# P08_RS485_RS232_CAN.net
KiCad netlist of a schematic drawn in Altium Designer
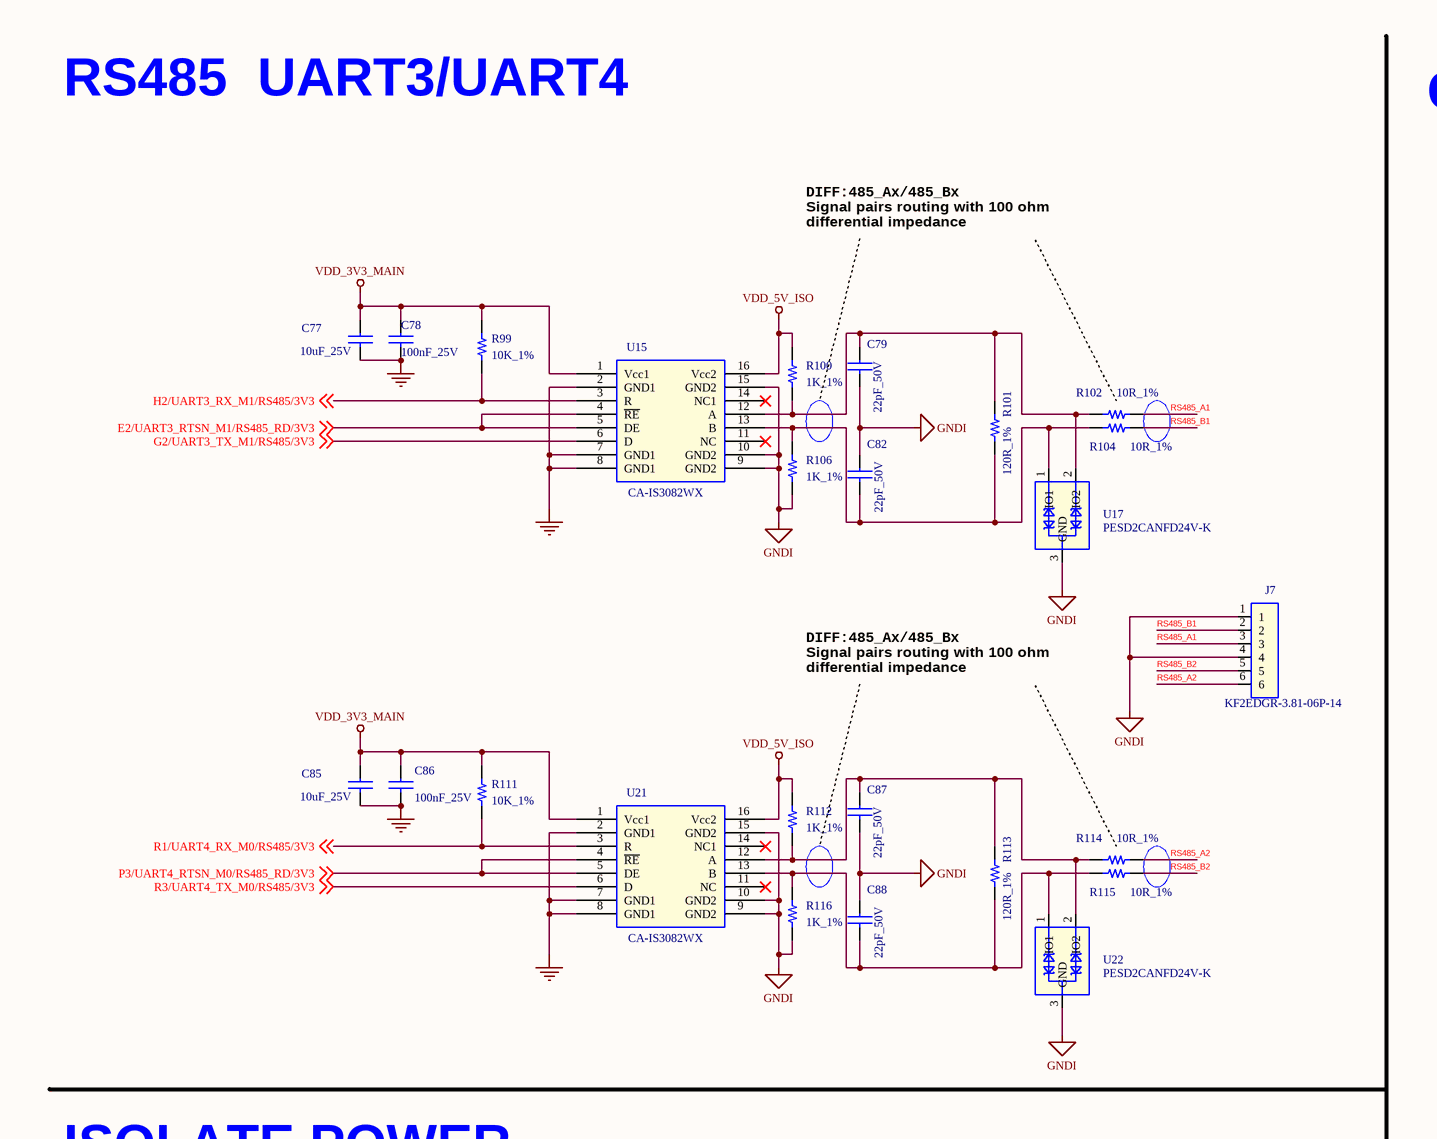
[diagram p0: P08_RS485_RS232_CAN.SchDoc, top left]
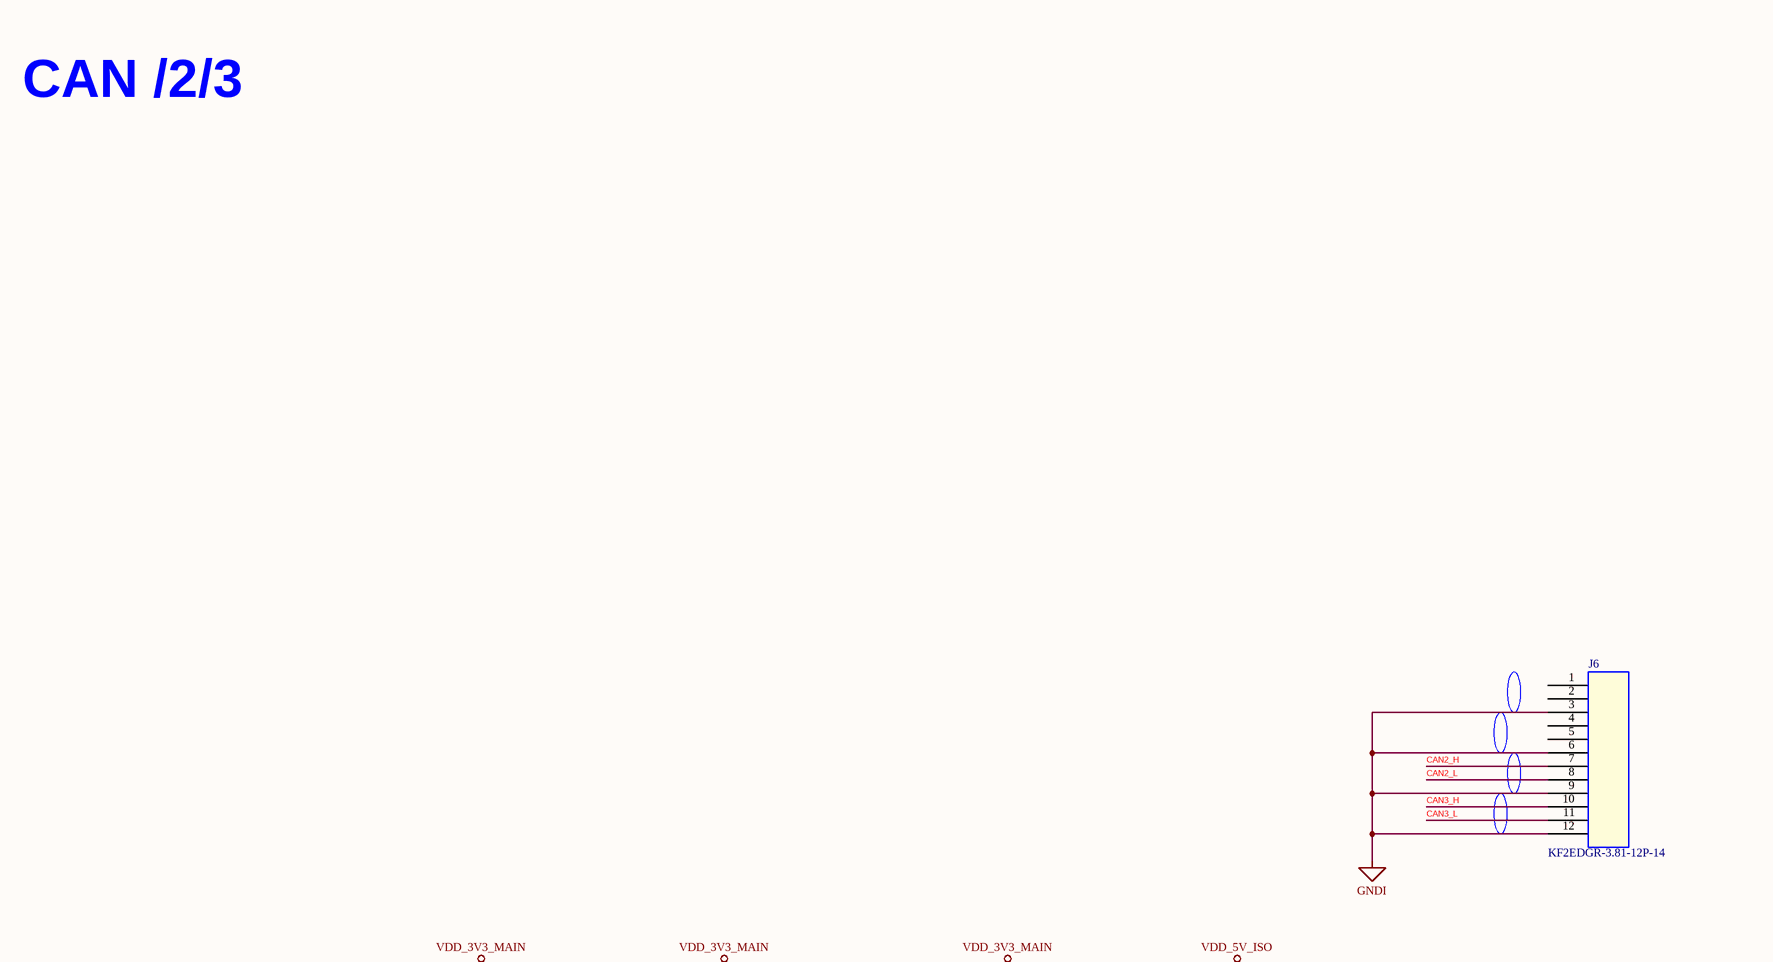
[diagram p1: P08_RS485_RS232_CAN.SchDoc, top right]
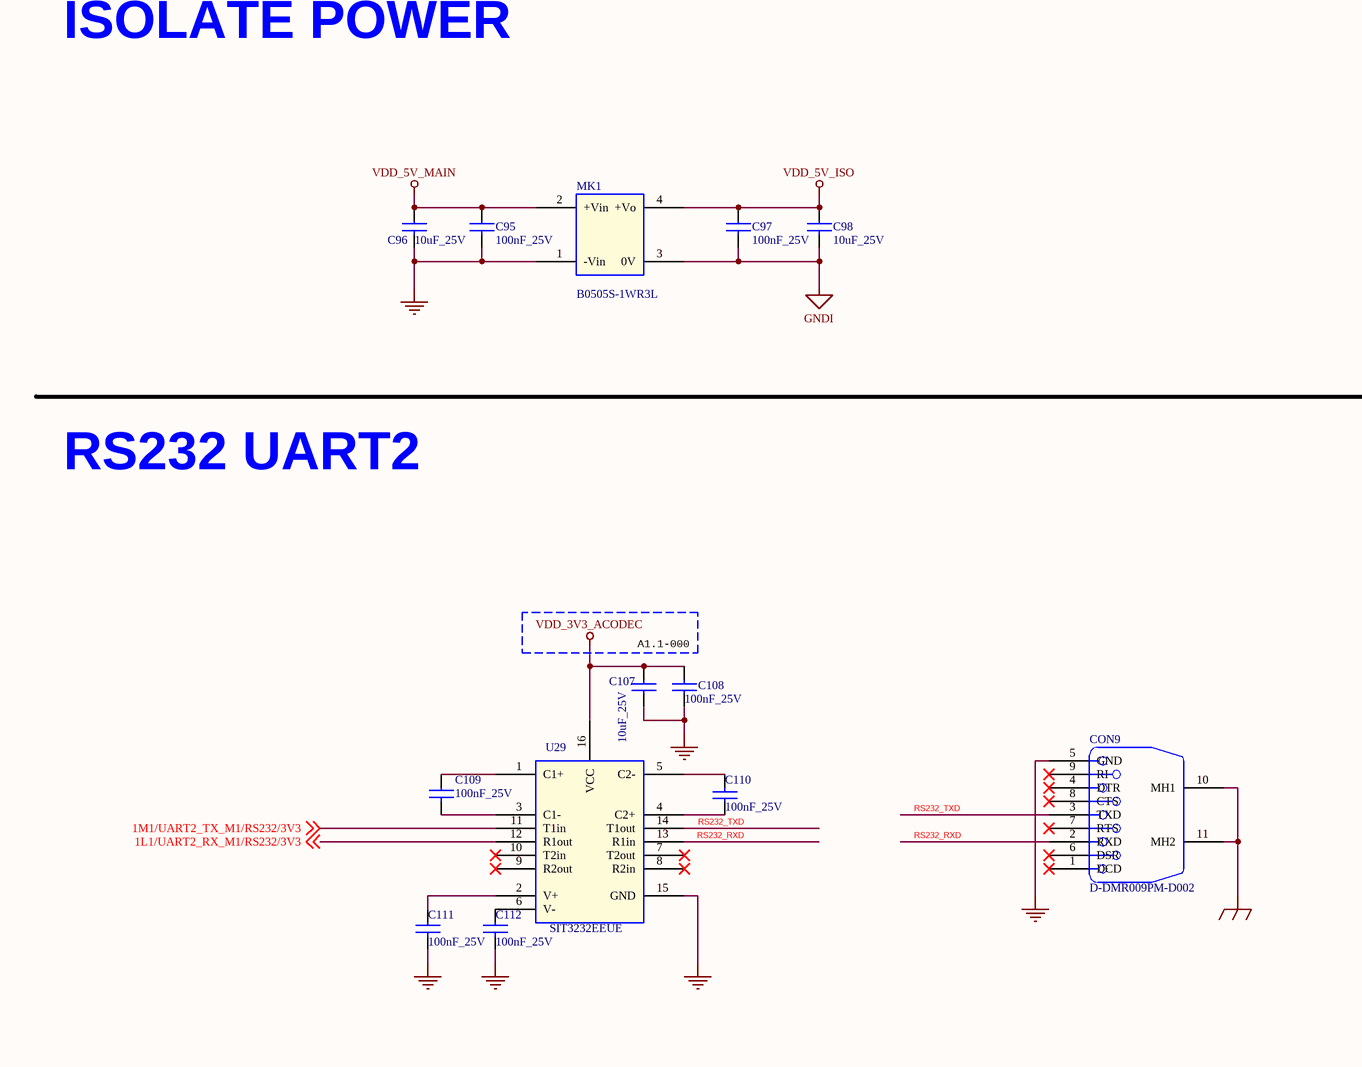
[diagram p2: P08_RS485_RS232_CAN.SchDoc, bottom left]
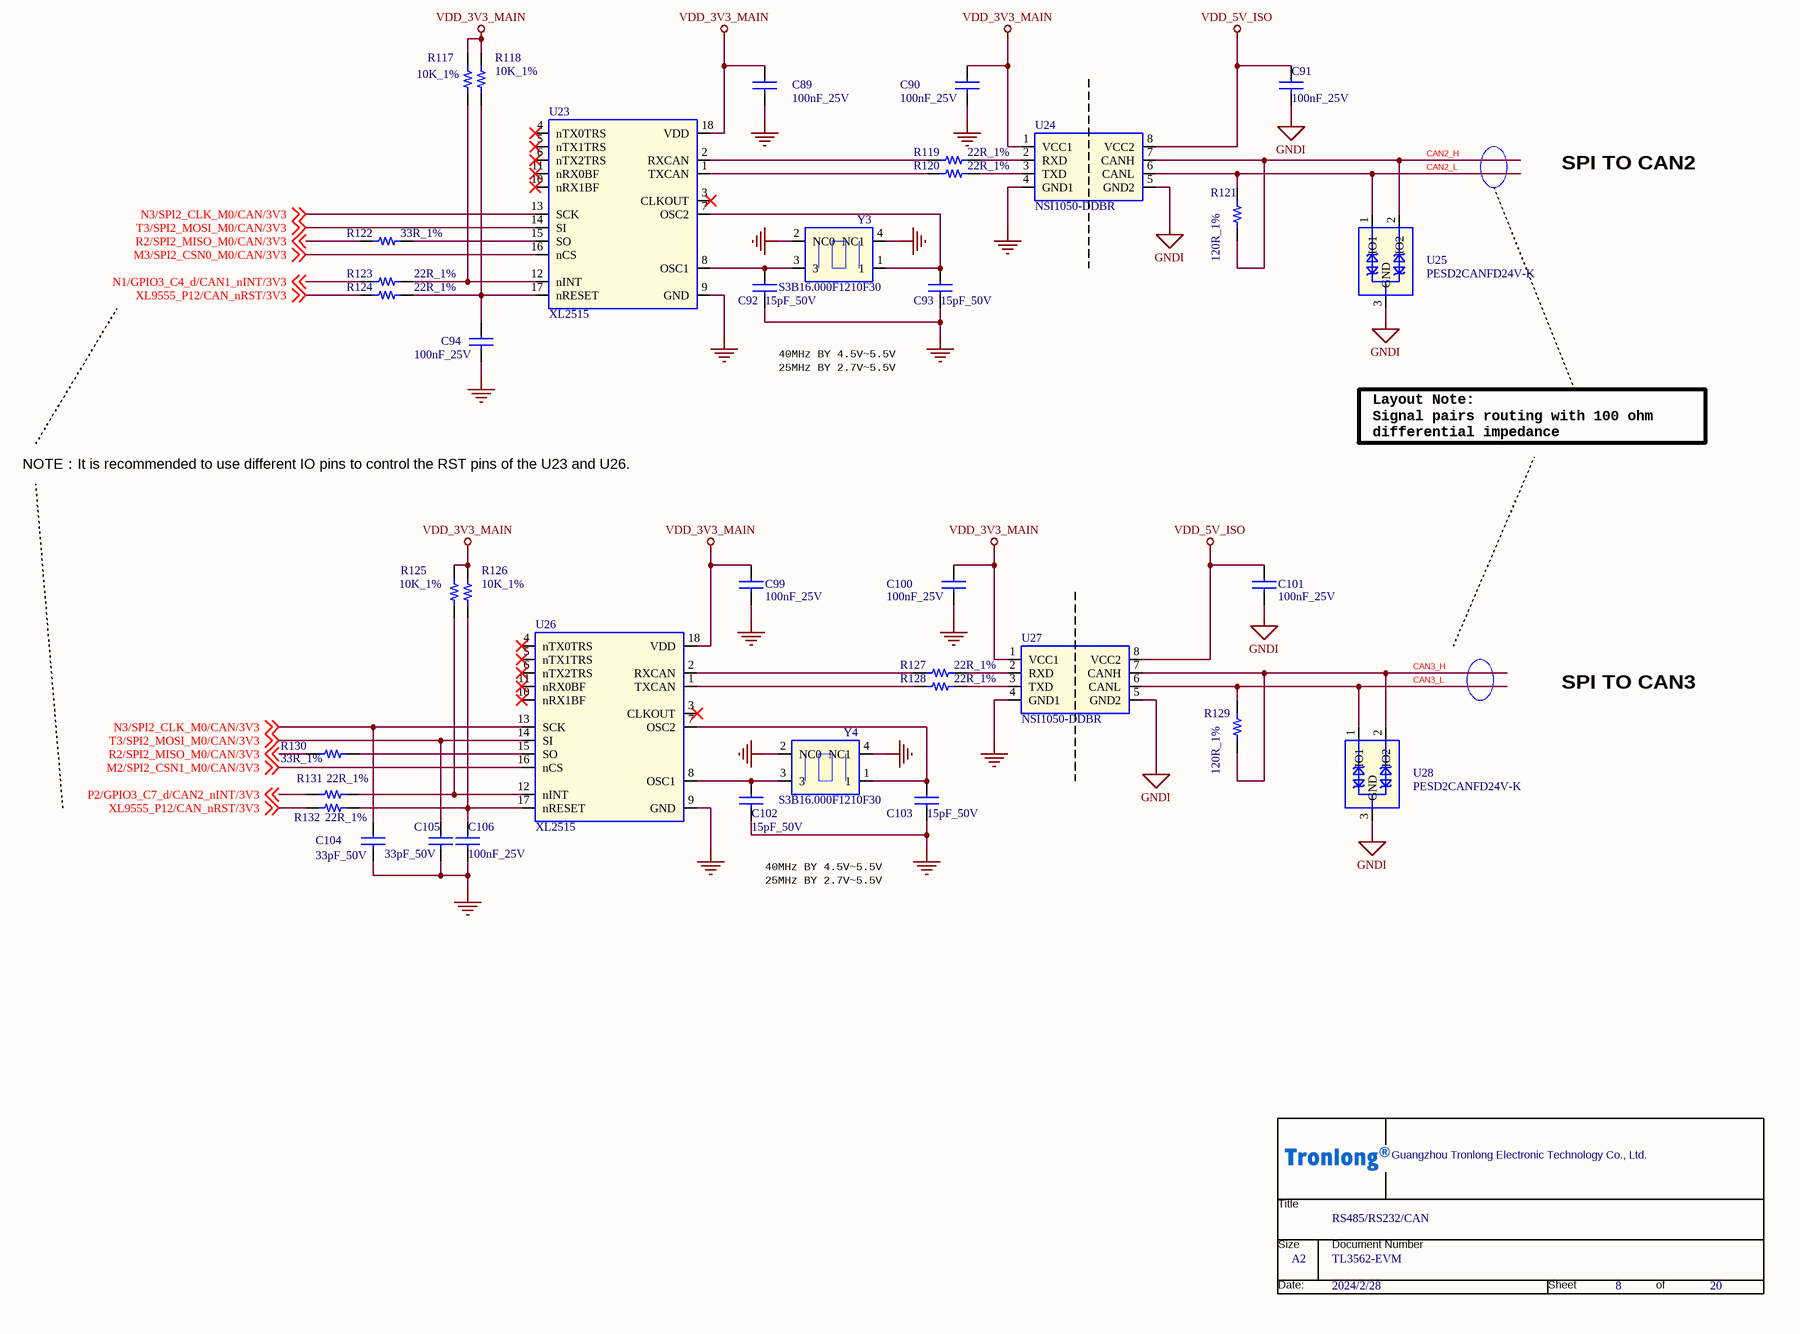
[diagram p3: P08_RS485_RS232_CAN.SchDoc, bottom right]

(export (version "E")
  (design (tool "Eeschema 10.0.6"))
  (components
    (comp (ref "C77")
      (value "10uF_25V")
      (footprint "C0603")
      (description "贴片陶瓷电容,10uF,10%,10V,X5R")
      (libsource (lib "*") (part "CAP NP_Dup3"))
    )
    (comp (ref "C78")
      (value "100nF_25V")
      (footprint "C0402")
      (description "贴片陶瓷电容,100nF,10%,25V,X5R")
      (libsource (lib "*") (part "CAP NP_Dup3"))
    )
    (comp (ref "C79")
      (value "22pF_50V")
      (footprint "C0603")
      (description "贴片陶瓷电容,22pF,5%,50V,C0G")
      (libsource (lib "*") (part "CAP NP_Dup3"))
    )
    (comp (ref "C82")
      (value "22pF_50V")
      (footprint "C0603")
      (description "贴片陶瓷电容,22pF,5%,50V,C0G")
      (libsource (lib "*") (part "CAP NP_Dup3"))
    )
    (comp (ref "C85")
      (value "10uF_25V")
      (footprint "C0603")
      (description "贴片陶瓷电容,10uF,10%,10V,X5R")
      (libsource (lib "*") (part "CAP NP_Dup3"))
    )
    (comp (ref "C86")
      (value "100nF_25V")
      (footprint "C0402")
      (description "贴片陶瓷电容,100nF,10%,25V,X5R")
      (libsource (lib "*") (part "CAP NP_Dup3"))
    )
    (comp (ref "C87")
      (value "22pF_50V")
      (footprint "C0603")
      (description "贴片陶瓷电容,22pF,5%,50V,C0G")
      (libsource (lib "*") (part "CAP NP_Dup3"))
    )
    (comp (ref "C88")
      (value "22pF_50V")
      (footprint "C0603")
      (description "贴片陶瓷电容,22pF,5%,50V,C0G")
      (libsource (lib "*") (part "CAP NP_Dup3"))
    )
    (comp (ref "C89")
      (value "100nF_25V")
      (footprint "C0402")
      (description "贴片陶瓷电容,100nF,10%,25V,X5R")
      (libsource (lib "*") (part "CAP NP_Dup1"))
    )
    (comp (ref "C90")
      (value "100nF_25V")
      (footprint "C0402")
      (description "贴片陶瓷电容,100nF,10%,25V,X5R")
      (libsource (lib "*") (part "CAP NP_Dup1"))
    )
    (comp (ref "C91")
      (value "100nF_25V")
      (footprint "C0402")
      (description "贴片陶瓷电容,100nF,10%,25V,X5R")
      (libsource (lib "*") (part "CAP NP_Dup1"))
    )
    (comp (ref "C92")
      (value "15pF_50V")
      (footprint "C0402")
      (description "贴片陶瓷电容,15pF,5%,50V,COG")
      (libsource (lib "*") (part "CAP NP_Dup1"))
    )
    (comp (ref "C93")
      (value "15pF_50V")
      (footprint "C0402")
      (description "贴片陶瓷电容,15pF,5%,50V,COG")
      (libsource (lib "*") (part "CAP NP_Dup1"))
    )
    (comp (ref "C94")
      (value "100nF_25V")
      (footprint "C0402")
      (description "贴片陶瓷电容,100nF,10%,25V,X5R")
      (libsource (lib "*") (part "CAP NP_Dup1"))
    )
    (comp (ref "C95")
      (value "100nF_25V")
      (footprint "C0402")
      (description "贴片陶瓷电容,100nF,10%,25V,X5R")
      (libsource (lib "*") (part "CAP NP_Dup3"))
    )
    (comp (ref "C96")
      (value "10uF_25V")
      (footprint "C0603")
      (description "贴片陶瓷电容,10uF,10%,10V,X5R")
      (libsource (lib "*") (part "CAP NP_Dup3"))
    )
    (comp (ref "C97")
      (value "100nF_25V")
      (footprint "C0402")
      (description "贴片陶瓷电容,100nF,10%,25V,X5R")
      (libsource (lib "*") (part "CAP NP_Dup3"))
    )
    (comp (ref "C98")
      (value "10uF_25V")
      (footprint "C0603")
      (description "贴片陶瓷电容,10uF,10%,10V,X5R")
      (libsource (lib "*") (part "CAP NP_Dup3"))
    )
    (comp (ref "C99")
      (value "100nF_25V")
      (footprint "C0402")
      (description "贴片陶瓷电容,100nF,10%,25V,X5R")
      (libsource (lib "*") (part "CAP NP_Dup1"))
    )
    (comp (ref "C100")
      (value "100nF_25V")
      (footprint "C0402")
      (description "贴片陶瓷电容,100nF,10%,25V,X5R")
      (libsource (lib "*") (part "CAP NP_Dup1"))
    )
    (comp (ref "C101")
      (value "100nF_25V")
      (footprint "C0402")
      (description "贴片陶瓷电容,100nF,10%,25V,X5R")
      (libsource (lib "*") (part "CAP NP_Dup1"))
    )
    (comp (ref "C102")
      (value "15pF_50V")
      (footprint "C0402")
      (description "贴片陶瓷电容,15pF,5%,50V,COG")
      (libsource (lib "*") (part "CAP NP_Dup1"))
    )
    (comp (ref "C103")
      (value "15pF_50V")
      (footprint "C0402")
      (description "贴片陶瓷电容,15pF,5%,50V,COG")
      (libsource (lib "*") (part "CAP NP_Dup1"))
    )
    (comp (ref "C104")
      (value "33pF_50V")
      (footprint "C0603")
      (description "贴片陶瓷电容,33pF,5%,50V,COG")
      (libsource (lib "*") (part "CAP NP_Dup1"))
    )
    (comp (ref "C105")
      (value "33pF_50V")
      (footprint "C0603")
      (description "贴片陶瓷电容,33pF,5%,50V,COG")
      (libsource (lib "*") (part "CAP NP_Dup1"))
    )
    (comp (ref "C106")
      (value "100nF_25V")
      (footprint "C0402")
      (description "贴片陶瓷电容,100nF,10%,25V,X5R")
      (libsource (lib "*") (part "CAP NP_Dup1"))
    )
    (comp (ref "C107")
      (value "10uF_25V")
      (footprint "C0603")
      (description "贴片陶瓷电容,10uF,10%,10V,X5R")
      (libsource (lib "*") (part "CAP NP_Dup3"))
    )
    (comp (ref "C108")
      (value "100nF_25V")
      (footprint "C0402")
      (description "贴片陶瓷电容,100nF,10%,25V,X5R")
      (libsource (lib "*") (part "CAP NP_Dup3"))
    )
    (comp (ref "C109")
      (value "100nF_25V")
      (footprint "C0402")
      (description "贴片陶瓷电容,100nF,10%,25V,X5R")
      (libsource (lib "*") (part "CAP NP_Dup3"))
    )
    (comp (ref "C110")
      (value "100nF_25V")
      (footprint "C0402")
      (description "贴片陶瓷电容,100nF,10%,25V,X5R")
      (libsource (lib "*") (part "CAP NP_Dup3"))
    )
    (comp (ref "C111")
      (value "100nF_25V")
      (footprint "C0402")
      (description "贴片陶瓷电容,100nF,10%,25V,X5R")
      (libsource (lib "*") (part "CAP NP_Dup3"))
    )
    (comp (ref "C112")
      (value "100nF_25V")
      (footprint "C0402")
      (description "贴片陶瓷电容,100nF,10%,25V,X5R")
      (libsource (lib "*") (part "CAP NP_Dup3"))
    )
    (comp (ref "CON9")
      (value "D-DMR009PM-D002")
      (footprint "CON_DB9")
      (description "DB9,9PIN,90度,公头,黑色,插件")
      (fields (field (name "MANUFACTURER") "深圳市灿科盟实业有限公司（ckmtw）"))
      (libsource (lib "*") (part "DB9_1"))
    )
    (comp (ref "J6")
      (value "KF2EDGR-3.81-12P-14")
      (footprint "KF2EDGR-3d81-12P")
      (description "端子座,12PIN,间距3.81MM,90度,插件")
      (fields
        (field (name "MANUFACTURER") "慈溪市科发电子有限公司（KEFA）")
        (field (name "MANUFACTURER PARTNUMBER") "KF2EDGR-3.81-12P")
      )
      (libsource (lib "*") (part "CON10_0"))
    )
    (comp (ref "J7")
      (value "KF2EDGR-3.81-06P-14")
      (footprint "kf2eg_3_81-6p")
      (description "端子座,6PIN,间距3.81MM,90度,插件")
      (fields
        (field (name "MANUFACTURER") "慈溪市科发电子有限公司（KEFA）")
        (field (name "MANUFACTURER PARTNUMBER") "KF2EDGR-3.81-06P")
      )
      (libsource (lib "*") (part "CON6"))
    )
    (comp (ref "MK1")
      (value "B0505S-1WR3L")
      (footprint "DIP4_B0505S_1W")
      (description "DC-DC隔离电源,B0505S-1WR3L,输入电压5V,输出电压5V,输出电流max/min=200/20mA,效率max/min=78/82")
      (fields (field (name "MANUFACTURER") "广州金升阳科技有限公司（MORNSUN）"))
      (libsource (lib "*") (part "B_S-2W_1"))
    )
    (comp (ref "R99")
      (value "10K_1%")
      (footprint "R0402")
      (description "贴片电阻,10K,±1%,1/16W")
      (libsource (lib "*") (part "Resistor_Dup3"))
    )
    (comp (ref "R100")
      (value "1K_1%")
      (footprint "R0402")
      (description "贴片电阻,1K,±1%,1/16W")
      (libsource (lib "*") (part "Resistor_Dup3"))
    )
    (comp (ref "R101")
      (value "120R_1%")
      (footprint "R0805")
      (description "贴片电阻,120R,±1%,1/8W")
      (libsource (lib "*") (part "Resistor_Dup3"))
    )
    (comp (ref "R102")
      (value "10R_1%")
      (footprint "R0603")
      (description "贴片电阻,10R,±1%,1/10W")
      (libsource (lib "*") (part "Resistor_Dup3"))
    )
    (comp (ref "R104")
      (value "10R_1%")
      (footprint "R0603")
      (description "贴片电阻,10R,±1%,1/10W")
      (libsource (lib "*") (part "Resistor_Dup3"))
    )
    (comp (ref "R106")
      (value "1K_1%")
      (footprint "R0402")
      (description "贴片电阻,1K,±1%,1/16W")
      (libsource (lib "*") (part "Resistor_Dup3"))
    )
    (comp (ref "R111")
      (value "10K_1%")
      (footprint "R0402")
      (description "贴片电阻,10K,±1%,1/16W")
      (libsource (lib "*") (part "Resistor_Dup3"))
    )
    (comp (ref "R112")
      (value "1K_1%")
      (footprint "R0402")
      (description "贴片电阻,1K,±1%,1/16W")
      (libsource (lib "*") (part "Resistor_Dup3"))
    )
    (comp (ref "R113")
      (value "120R_1%")
      (footprint "R0805")
      (description "贴片电阻,120R,±1%,1/8W")
      (libsource (lib "*") (part "Resistor_Dup3"))
    )
    (comp (ref "R114")
      (value "10R_1%")
      (footprint "R0603")
      (description "贴片电阻,10R,±1%,1/10W")
      (libsource (lib "*") (part "Resistor_Dup3"))
    )
    (comp (ref "R115")
      (value "10R_1%")
      (footprint "R0603")
      (description "贴片电阻,10R,±1%,1/10W")
      (libsource (lib "*") (part "Resistor_Dup3"))
    )
    (comp (ref "R116")
      (value "1K_1%")
      (footprint "R0402")
      (description "贴片电阻,1K,±1%,1/16W")
      (libsource (lib "*") (part "Resistor_Dup3"))
    )
    (comp (ref "R117")
      (value "10K_1%")
      (footprint "R0402")
      (description "贴片电阻,10K,±1%,1/16W")
      (libsource (lib "*") (part "R 1%"))
    )
    (comp (ref "R118")
      (value "10K_1%")
      (footprint "R0402")
      (description "贴片电阻,10K,±1%,1/16W")
      (libsource (lib "*") (part "R 1%"))
    )
    (comp (ref "R119")
      (value "22R_1%")
      (footprint "R0402")
      (description "贴片电阻,22R,±1%,1/16W")
      (libsource (lib "*") (part "R 1%"))
    )
    (comp (ref "R120")
      (value "22R_1%")
      (footprint "R0402")
      (description "贴片电阻,22R,±1%,1/16W")
      (libsource (lib "*") (part "R 1%"))
    )
    (comp (ref "R121")
      (value "120R_1%")
      (footprint "R0805")
      (description "贴片电阻,120R,±1%,1/8W")
      (libsource (lib "*") (part "R 1%"))
    )
    (comp (ref "R122")
      (value "33R_1%")
      (footprint "R0402")
      (description "贴片电阻,33R,±1%,1/16W")
      (libsource (lib "*") (part "R 1%"))
    )
    (comp (ref "R123")
      (value "22R_1%")
      (footprint "R0402")
      (description "贴片电阻,22R,±1%,1/16W")
      (libsource (lib "*") (part "R 1%"))
    )
    (comp (ref "R124")
      (value "22R_1%")
      (footprint "R0402")
      (description "贴片电阻,22R,±1%,1/16W")
      (libsource (lib "*") (part "R 1%"))
    )
    (comp (ref "R125")
      (value "10K_1%")
      (footprint "R0402")
      (description "贴片电阻,10K,±1%,1/16W")
      (libsource (lib "*") (part "R 1%"))
    )
    (comp (ref "R126")
      (value "10K_1%")
      (footprint "R0402")
      (description "贴片电阻,10K,±1%,1/16W")
      (libsource (lib "*") (part "R 1%"))
    )
    (comp (ref "R127")
      (value "22R_1%")
      (footprint "R0402")
      (description "贴片电阻,22R,±1%,1/16W")
      (libsource (lib "*") (part "R 1%"))
    )
    (comp (ref "R128")
      (value "22R_1%")
      (footprint "R0402")
      (description "贴片电阻,22R,±1%,1/16W")
      (libsource (lib "*") (part "R 1%"))
    )
    (comp (ref "R129")
      (value "120R_1%")
      (footprint "R0805")
      (description "贴片电阻,120R,±1%,1/8W")
      (libsource (lib "*") (part "R 1%"))
    )
    (comp (ref "R130")
      (value "33R_1%")
      (footprint "R0402")
      (description "贴片电阻,33R,±1%,1/16W")
      (libsource (lib "*") (part "R 1%"))
    )
    (comp (ref "R131")
      (value "22R_1%")
      (footprint "R0402")
      (description "贴片电阻,22R,±1%,1/16W")
      (libsource (lib "*") (part "R 1%"))
    )
    (comp (ref "R132")
      (value "22R_1%")
      (footprint "R0402")
      (description "贴片电阻,22R,±1%,1/16W")
      (libsource (lib "*") (part "R 1%"))
    )
    (comp (ref "U15")
      (value "CA-IS3082WX")
      (footprint "SOIC16")
      (description "CA-IS308x 隔离 5kV 全/半双工 RS485 收发器")
      (fields (field (name "MANUFACTURER") "上海川土微电子有限公司（Chipanalog）"))
      (libsource (lib "*") (part "ISO3082"))
    )
    (comp (ref "U17")
      (value "PESD2CANFD24V-K")
      (footprint "SOT23-3")
      (description "TVS二极管")
      (fields (field (name "MANUFACTURER") "派克微电子（深圳）有限公司"))
      (libsource (lib "*") (part "PSM712"))
    )
    (comp (ref "U21")
      (value "CA-IS3082WX")
      (footprint "SOIC16")
      (description "CA-IS308x 隔离 5kV 全/半双工 RS485 收发器")
      (fields (field (name "MANUFACTURER") "上海川土微电子有限公司（Chipanalog）"))
      (libsource (lib "*") (part "ISO3082"))
    )
    (comp (ref "U22")
      (value "PESD2CANFD24V-K")
      (footprint "SOT23-3")
      (description "TVS二极管")
      (fields (field (name "MANUFACTURER") "派克微电子（深圳）有限公司"))
      (libsource (lib "*") (part "PSM712"))
    )
    (comp (ref "U23")
      (value "XL2515")
      (footprint "SOIC18")
      (description "带 SPI 接口的独立 CAN 控制器")
      (fields (field (name "MANUFACTURER") "信路达信息技术（厦门）有限（xinluda）"))
      (libsource (lib "*") (part "MCP2510/2515_3"))
    )
    (comp (ref "U24")
      (value "NSI1050-DDBR")
      (footprint "SOP8")
      (description "隔离CAN收发器")
      (fields (field (name "MANUFACTURER") "苏州纳芯微电子股份有限公司（NOVOSENSE）"))
      (libsource (lib "*") (part "ISO1050"))
    )
    (comp (ref "U25")
      (value "PESD2CANFD24V-K")
      (footprint "SOT23-3")
      (description "TVS二极管")
      (fields (field (name "MANUFACTURER") "派克微电子（深圳）有限公司"))
      (libsource (lib "*") (part "PSM712"))
    )
    (comp (ref "U26")
      (value "XL2515")
      (footprint "SOIC18")
      (description "带 SPI 接口的独立 CAN 控制器")
      (fields (field (name "MANUFACTURER") "信路达信息技术（厦门）有限（xinluda）"))
      (libsource (lib "*") (part "MCP2510/2515_2"))
    )
    (comp (ref "U27")
      (value "NSI1050-DDBR")
      (footprint "SOP8")
      (description "隔离CAN收发器")
      (fields (field (name "MANUFACTURER") "苏州纳芯微电子股份有限公司（NOVOSENSE）"))
      (libsource (lib "*") (part "ISO1050"))
    )
    (comp (ref "U28")
      (value "PESD2CANFD24V-K")
      (footprint "SOT23-3")
      (description "TVS二极管")
      (fields (field (name "MANUFACTURER") "派克微电子（深圳）有限公司"))
      (libsource (lib "*") (part "PSM712"))
    )
    (comp (ref "U29")
      (value "SIT3232EEUE")
      (footprint "TSSOP16_PW16")
      (description "RS232收发器")
      (fields (field (name "MANUFACTURER") "江苏芯力特电子科技有限公司（SIT）"))
      (libsource (lib "*") (part "MAX232A_0"))
    )
    (comp (ref "Y3")
      (value "S3B16.000F1210F30")
      (footprint "SMD_3225")
      (description "四脚无源晶振,16MHz,±10ppm,12pF,60Ω,±30ppm")
      (fields (field (name "MANUFACTURER") "深圳市星通时频电子有限公司公司（JSCJ）"))
      (libsource (lib "*") (part "CRYSTAL"))
    )
    (comp (ref "Y4")
      (value "S3B16.000F1210F30")
      (footprint "SMD_3225")
      (description "四脚无源晶振,16MHz,±10ppm,12pF,60Ω,±30ppm")
      (fields (field (name "MANUFACTURER") "深圳市星通时频电子有限公司公司（JSCJ）"))
      (libsource (lib "*") (part "CRYSTAL"))
    )
  )
  (nets
    (net (code "1") (name "/CAN2_H") (class "Default")
      (node (ref "J6") (pin "7") (pinfunction "7_7") (pintype "passive"))
      (node (ref "R121") (pin "1") (pinfunction "1_1") (pintype "passive"))
      (node (ref "U24") (pin "7") (pinfunction "CANH_7") (pintype "passive"))
      (node (ref "U25") (pin "2") (pinfunction "IO2_2") (pintype "passive"))
    )
    (net (code "2") (name "/CAN2_L") (class "Default")
      (node (ref "J6") (pin "8") (pinfunction "8_8") (pintype "passive"))
      (node (ref "R121") (pin "2") (pinfunction "2_2") (pintype "passive"))
      (node (ref "U24") (pin "6") (pinfunction "CANL_6") (pintype "passive"))
      (node (ref "U25") (pin "1") (pinfunction "IO1_1") (pintype "passive"))
    )
    (net (code "3") (name "/CAN3_H") (class "Default")
      (node (ref "J6") (pin "10") (pinfunction "10_10") (pintype "passive"))
      (node (ref "R129") (pin "1") (pinfunction "1_1") (pintype "passive"))
      (node (ref "U27") (pin "7") (pinfunction "CANH_7") (pintype "passive"))
      (node (ref "U28") (pin "2") (pinfunction "IO2_2") (pintype "passive"))
    )
    (net (code "4") (name "/CAN3_L") (class "Default")
      (node (ref "J6") (pin "11") (pinfunction "11_11") (pintype "passive"))
      (node (ref "R129") (pin "2") (pinfunction "2_2") (pintype "passive"))
      (node (ref "U27") (pin "6") (pinfunction "CANL_6") (pintype "passive"))
      (node (ref "U28") (pin "1") (pinfunction "IO1_1") (pintype "passive"))
    )
    (net (code "5") (name "/RS232_RXD") (class "Default")
      (node (ref "CON9") (pin "2") (pinfunction "RXD_2") (pintype "passive"))
      (node (ref "U29") (pin "13") (pinfunction "R1in_13") (pintype "passive"))
    )
    (net (code "6") (name "/RS232_TXD") (class "Default")
      (node (ref "CON9") (pin "3") (pinfunction "TXD_3") (pintype "passive"))
      (node (ref "U29") (pin "14") (pinfunction "T1out_14") (pintype "passive"))
    )
    (net (code "7") (name "/RS485_A1") (class "Default")
      (node (ref "J7") (pin "3") (pinfunction "3_3") (pintype "passive"))
      (node (ref "R102") (pin "1") (pinfunction "1_1") (pintype "passive"))
    )
    (net (code "8") (name "/RS485_A2") (class "Default")
      (node (ref "J7") (pin "6") (pinfunction "6_6") (pintype "passive"))
      (node (ref "R114") (pin "1") (pinfunction "1_1") (pintype "passive"))
    )
    (net (code "9") (name "/RS485_B1") (class "Default")
      (node (ref "J7") (pin "2") (pinfunction "2_2") (pintype "passive"))
      (node (ref "R104") (pin "1") (pinfunction "1_1") (pintype "passive"))
    )
    (net (code "10") (name "/RS485_B2") (class "Default")
      (node (ref "J7") (pin "5") (pinfunction "5_5") (pintype "passive"))
      (node (ref "R115") (pin "1") (pinfunction "1_1") (pintype "passive"))
    )
    (net (code "11") (name "1L1{slash}UART2_RX_M1{slash}RS232{slash}3V3") (class "Default")
      (node (ref "U29") (pin "12") (pinfunction "R1out_12") (pintype "passive"))
    )
    (net (code "12") (name "1M1{slash}UART2_TX_M1{slash}RS232{slash}3V3") (class "Default")
      (node (ref "U29") (pin "11") (pinfunction "T1in_11") (pintype "passive"))
    )
    (net (code "13") (name "E2{slash}UART3_RTSN_M1{slash}RS485_RD{slash}3V3") (class "Default")
      (node (ref "U15") (pin "4") (pinfunction "~{RE}_4") (pintype "passive"))
      (node (ref "U15") (pin "5") (pinfunction "DE_5") (pintype "passive"))
    )
    (net (code "14") (name "EGND") (class "Default")
      (node (ref "CON9") (pin "10") (pinfunction "MH1_10") (pintype "passive"))
      (node (ref "CON9") (pin "11") (pinfunction "MH2_11") (pintype "passive"))
    )
    (net (code "15") (name "G2{slash}UART3_TX_M1{slash}RS485{slash}3V3") (class "Default")
      (node (ref "U15") (pin "6") (pinfunction "D_6") (pintype "passive"))
    )
    (net (code "16") (name "GND") (class "Default")
      (node (ref "C100") (pin "2") (pinfunction "2_2") (pintype "passive"))
      (node (ref "C102") (pin "2") (pinfunction "2_2") (pintype "passive"))
      (node (ref "C103") (pin "2") (pinfunction "2_2") (pintype "passive"))
      (node (ref "C104") (pin "2") (pinfunction "2_2") (pintype "passive"))
      (node (ref "C105") (pin "2") (pinfunction "2_2") (pintype "passive"))
      (node (ref "C106") (pin "2") (pinfunction "2_2") (pintype "passive"))
      (node (ref "C107") (pin "1") (pinfunction "1_1") (pintype "passive"))
      (node (ref "C108") (pin "1") (pinfunction "1_1") (pintype "passive"))
      (node (ref "C111") (pin "2") (pinfunction "2_2") (pintype "passive"))
      (node (ref "C112") (pin "2") (pinfunction "2_2") (pintype "passive"))
      (node (ref "C77") (pin "2") (pinfunction "2_2") (pintype "passive"))
      (node (ref "C78") (pin "2") (pinfunction "2_2") (pintype "passive"))
      (node (ref "C85") (pin "2") (pinfunction "2_2") (pintype "passive"))
      (node (ref "C86") (pin "2") (pinfunction "2_2") (pintype "passive"))
      (node (ref "C89") (pin "2") (pinfunction "2_2") (pintype "passive"))
      (node (ref "C90") (pin "2") (pinfunction "2_2") (pintype "passive"))
      (node (ref "C92") (pin "2") (pinfunction "2_2") (pintype "passive"))
      (node (ref "C93") (pin "2") (pinfunction "2_2") (pintype "passive"))
      (node (ref "C94") (pin "2") (pinfunction "2_2") (pintype "passive"))
      (node (ref "C95") (pin "2") (pinfunction "2_2") (pintype "passive"))
      (node (ref "C96") (pin "2") (pinfunction "2_2") (pintype "passive"))
      (node (ref "C99") (pin "2") (pinfunction "2_2") (pintype "passive"))
      (node (ref "CON9") (pin "5") (pinfunction "GND_5") (pintype "power_in"))
      (node (ref "MK1") (pin "1") (pinfunction "-Vin_1") (pintype "passive"))
      (node (ref "U15") (pin "2") (pinfunction "GND1_2") (pintype "power_in"))
      (node (ref "U15") (pin "7") (pinfunction "GND1_7") (pintype "power_in"))
      (node (ref "U15") (pin "8") (pinfunction "GND1_8") (pintype "power_in"))
      (node (ref "U21") (pin "2") (pinfunction "GND1_2") (pintype "power_in"))
      (node (ref "U21") (pin "7") (pinfunction "GND1_7") (pintype "power_in"))
      (node (ref "U21") (pin "8") (pinfunction "GND1_8") (pintype "power_in"))
      (node (ref "U23") (pin "9") (pinfunction "GND_9") (pintype "power_in"))
      (node (ref "U24") (pin "4") (pinfunction "GND1_4") (pintype "power_in"))
      (node (ref "U26") (pin "9") (pinfunction "GND_9") (pintype "power_in"))
      (node (ref "U27") (pin "4") (pinfunction "GND1_4") (pintype "power_in"))
      (node (ref "U29") (pin "15") (pinfunction "GND_15") (pintype "passive"))
      (node (ref "Y3") (pin "2") (pinfunction "NC0_2") (pintype "passive"))
      (node (ref "Y3") (pin "4") (pinfunction "NC1_4") (pintype "passive"))
      (node (ref "Y4") (pin "2") (pinfunction "NC0_2") (pintype "passive"))
      (node (ref "Y4") (pin "4") (pinfunction "NC1_4") (pintype "passive"))
    )
    (net (code "17") (name "GNDI") (class "Default")
      (node (ref "C101") (pin "2") (pinfunction "2_2") (pintype "passive"))
      (node (ref "C79") (pin "2") (pinfunction "2_2") (pintype "passive"))
      (node (ref "C82") (pin "1") (pinfunction "1_1") (pintype "passive"))
      (node (ref "C87") (pin "2") (pinfunction "2_2") (pintype "passive"))
      (node (ref "C88") (pin "1") (pinfunction "1_1") (pintype "passive"))
      (node (ref "C91") (pin "2") (pinfunction "2_2") (pintype "passive"))
      (node (ref "C97") (pin "2") (pinfunction "2_2") (pintype "passive"))
      (node (ref "C98") (pin "2") (pinfunction "2_2") (pintype "passive"))
      (node (ref "J6") (pin "12") (pinfunction "12_12") (pintype "passive"))
      (node (ref "J6") (pin "3") (pinfunction "3_3") (pintype "passive"))
      (node (ref "J6") (pin "6") (pinfunction "6_6") (pintype "passive"))
      (node (ref "J6") (pin "9") (pinfunction "9_9") (pintype "passive"))
      (node (ref "J7") (pin "1") (pinfunction "1_1") (pintype "passive"))
      (node (ref "J7") (pin "4") (pinfunction "4_4") (pintype "passive"))
      (node (ref "MK1") (pin "3") (pinfunction "0V_3") (pintype "passive"))
      (node (ref "R106") (pin "2") (pinfunction "2_2") (pintype "passive"))
      (node (ref "R116") (pin "2") (pinfunction "2_2") (pintype "passive"))
      (node (ref "U15") (pin "10") (pinfunction "GND2_10") (pintype "power_in"))
      (node (ref "U15") (pin "15") (pinfunction "GND2_15") (pintype "power_in"))
      (node (ref "U15") (pin "9") (pinfunction "GND2_9") (pintype "power_in"))
      (node (ref "U17") (pin "3") (pinfunction "GND_3") (pintype "passive"))
      (node (ref "U21") (pin "10") (pinfunction "GND2_10") (pintype "power_in"))
      (node (ref "U21") (pin "15") (pinfunction "GND2_15") (pintype "power_in"))
      (node (ref "U21") (pin "9") (pinfunction "GND2_9") (pintype "power_in"))
      (node (ref "U22") (pin "3") (pinfunction "GND_3") (pintype "passive"))
      (node (ref "U24") (pin "5") (pinfunction "GND2_5") (pintype "power_in"))
      (node (ref "U25") (pin "3") (pinfunction "GND_3") (pintype "passive"))
      (node (ref "U27") (pin "5") (pinfunction "GND2_5") (pintype "power_in"))
      (node (ref "U28") (pin "3") (pinfunction "GND_3") (pintype "passive"))
    )
    (net (code "18") (name "H2{slash}UART3_RX_M1{slash}RS485{slash}3V3") (class "Default")
      (node (ref "R99") (pin "2") (pinfunction "2_2") (pintype "passive"))
      (node (ref "U15") (pin "3") (pinfunction "R_3") (pintype "passive"))
    )
    (net (code "19") (name "M2{slash}SPI2_CSN1_M0{slash}CAN{slash}3V3") (class "Default")
      (node (ref "U26") (pin "16") (pinfunction "nCS_16") (pintype "passive"))
    )
    (net (code "20") (name "M3{slash}SPI2_CSN0_M0{slash}CAN{slash}3V3") (class "Default")
      (node (ref "U23") (pin "16") (pinfunction "nCS_16") (pintype "passive"))
    )
    (net (code "21") (name "N1{slash}GPIO3_C4_d{slash}CAN1_nINT{slash}3V3") (class "Default")
      (node (ref "R123") (pin "1") (pinfunction "1_1") (pintype "passive"))
    )
    (net (code "22") (name "N3{slash}SPI2_CLK_M0{slash}CAN{slash}3V3") (class "Default")
      (node (ref "C104") (pin "1") (pinfunction "1_1") (pintype "passive"))
      (node (ref "U23") (pin "13") (pinfunction "SCK_13") (pintype "passive"))
      (node (ref "U26") (pin "13") (pinfunction "SCK_13") (pintype "passive"))
    )
    (net (code "23") (name "Net-(U15-A)") (class "Default")
      (node (ref "C79") (pin "1") (pinfunction "1_1") (pintype "passive"))
      (node (ref "R100") (pin "2") (pinfunction "2_2") (pintype "passive"))
      (node (ref "R101") (pin "1") (pinfunction "1_1") (pintype "passive"))
      (node (ref "R102") (pin "2") (pinfunction "2_2") (pintype "passive"))
      (node (ref "U15") (pin "12") (pinfunction "A_12") (pintype "passive"))
      (node (ref "U17") (pin "2") (pinfunction "IO2_2") (pintype "passive"))
    )
    (net (code "24") (name "Net-(U15-B)") (class "Default")
      (node (ref "C82") (pin "2") (pinfunction "2_2") (pintype "passive"))
      (node (ref "R101") (pin "2") (pinfunction "2_2") (pintype "passive"))
      (node (ref "R104") (pin "2") (pinfunction "2_2") (pintype "passive"))
      (node (ref "R106") (pin "1") (pinfunction "1_1") (pintype "passive"))
      (node (ref "U15") (pin "13") (pinfunction "B_13") (pintype "passive"))
      (node (ref "U17") (pin "1") (pinfunction "IO1_1") (pintype "passive"))
    )
    (net (code "25") (name "Net-(U21-A)") (class "Default")
      (node (ref "C87") (pin "1") (pinfunction "1_1") (pintype "passive"))
      (node (ref "R112") (pin "2") (pinfunction "2_2") (pintype "passive"))
      (node (ref "R113") (pin "1") (pinfunction "1_1") (pintype "passive"))
      (node (ref "R114") (pin "2") (pinfunction "2_2") (pintype "passive"))
      (node (ref "U21") (pin "12") (pinfunction "A_12") (pintype "passive"))
      (node (ref "U22") (pin "2") (pinfunction "IO2_2") (pintype "passive"))
    )
    (net (code "26") (name "Net-(U21-B)") (class "Default")
      (node (ref "C88") (pin "2") (pinfunction "2_2") (pintype "passive"))
      (node (ref "R113") (pin "2") (pinfunction "2_2") (pintype "passive"))
      (node (ref "R115") (pin "2") (pinfunction "2_2") (pintype "passive"))
      (node (ref "R116") (pin "1") (pinfunction "1_1") (pintype "passive"))
      (node (ref "U21") (pin "13") (pinfunction "B_13") (pintype "passive"))
      (node (ref "U22") (pin "1") (pinfunction "IO1_1") (pintype "passive"))
    )
    (net (code "27") (name "Net-(U23-OSC1)") (class "Default")
      (node (ref "C92") (pin "1") (pinfunction "1_1") (pintype "passive"))
      (node (ref "U23") (pin "8") (pinfunction "OSC1_8") (pintype "passive"))
      (node (ref "Y3") (pin "3") (pinfunction "3_3") (pintype "passive"))
    )
    (net (code "28") (name "Net-(U23-OSC2)") (class "Default")
      (node (ref "C93") (pin "1") (pinfunction "1_1") (pintype "passive"))
      (node (ref "U23") (pin "7") (pinfunction "OSC2_7") (pintype "passive"))
      (node (ref "Y3") (pin "1") (pinfunction "1_1") (pintype "passive"))
    )
    (net (code "29") (name "Net-(U23-RXCAN)") (class "Default")
      (node (ref "R119") (pin "1") (pinfunction "1_1") (pintype "passive"))
      (node (ref "U23") (pin "2") (pinfunction "RXCAN_2") (pintype "passive"))
    )
    (net (code "30") (name "Net-(U23-SO)") (class "Default")
      (node (ref "R122") (pin "2") (pinfunction "2_2") (pintype "passive"))
      (node (ref "U23") (pin "15") (pinfunction "SO_15") (pintype "passive"))
    )
    (net (code "31") (name "Net-(U23-TXCAN)") (class "Default")
      (node (ref "R120") (pin "1") (pinfunction "1_1") (pintype "passive"))
      (node (ref "U23") (pin "1") (pinfunction "TXCAN_1") (pintype "passive"))
    )
    (net (code "32") (name "Net-(U23-nINT)") (class "Default")
      (node (ref "R117") (pin "1") (pinfunction "1_1") (pintype "passive"))
      (node (ref "R123") (pin "2") (pinfunction "2_2") (pintype "passive"))
      (node (ref "U23") (pin "12") (pinfunction "nINT_12") (pintype "passive"))
    )
    (net (code "33") (name "Net-(U23-nRESET)") (class "Default")
      (node (ref "C94") (pin "1") (pinfunction "1_1") (pintype "passive"))
      (node (ref "R118") (pin "1") (pinfunction "1_1") (pintype "passive"))
      (node (ref "R124") (pin "2") (pinfunction "2_2") (pintype "passive"))
      (node (ref "U23") (pin "17") (pinfunction "nRESET_17") (pintype "passive"))
    )
    (net (code "34") (name "Net-(U24-RXD)") (class "Default")
      (node (ref "R119") (pin "2") (pinfunction "2_2") (pintype "passive"))
      (node (ref "U24") (pin "2") (pinfunction "RXD_2") (pintype "passive"))
    )
    (net (code "35") (name "Net-(U24-TXD)") (class "Default")
      (node (ref "R120") (pin "2") (pinfunction "2_2") (pintype "passive"))
      (node (ref "U24") (pin "3") (pinfunction "TXD_3") (pintype "passive"))
    )
    (net (code "36") (name "Net-(U26-OSC1)") (class "Default")
      (node (ref "C102") (pin "1") (pinfunction "1_1") (pintype "passive"))
      (node (ref "U26") (pin "8") (pinfunction "OSC1_8") (pintype "passive"))
      (node (ref "Y4") (pin "3") (pinfunction "3_3") (pintype "passive"))
    )
    (net (code "37") (name "Net-(U26-OSC2)") (class "Default")
      (node (ref "C103") (pin "1") (pinfunction "1_1") (pintype "passive"))
      (node (ref "U26") (pin "7") (pinfunction "OSC2_7") (pintype "passive"))
      (node (ref "Y4") (pin "1") (pinfunction "1_1") (pintype "passive"))
    )
    (net (code "38") (name "Net-(U26-RXCAN)") (class "Default")
      (node (ref "R127") (pin "1") (pinfunction "1_1") (pintype "passive"))
      (node (ref "U26") (pin "2") (pinfunction "RXCAN_2") (pintype "passive"))
    )
    (net (code "39") (name "Net-(U26-SO)") (class "Default")
      (node (ref "R130") (pin "2") (pinfunction "2_2") (pintype "passive"))
      (node (ref "U26") (pin "15") (pinfunction "SO_15") (pintype "passive"))
    )
    (net (code "40") (name "Net-(U26-TXCAN)") (class "Default")
      (node (ref "R128") (pin "1") (pinfunction "1_1") (pintype "passive"))
      (node (ref "U26") (pin "1") (pinfunction "TXCAN_1") (pintype "passive"))
    )
    (net (code "41") (name "Net-(U26-nINT)") (class "Default")
      (node (ref "R125") (pin "1") (pinfunction "1_1") (pintype "passive"))
      (node (ref "R131") (pin "2") (pinfunction "2_2") (pintype "passive"))
      (node (ref "U26") (pin "12") (pinfunction "nINT_12") (pintype "passive"))
    )
    (net (code "42") (name "Net-(U26-nRESET)") (class "Default")
      (node (ref "C106") (pin "1") (pinfunction "1_1") (pintype "passive"))
      (node (ref "R126") (pin "1") (pinfunction "1_1") (pintype "passive"))
      (node (ref "R132") (pin "2") (pinfunction "2_2") (pintype "passive"))
      (node (ref "U26") (pin "17") (pinfunction "nRESET_17") (pintype "passive"))
    )
    (net (code "43") (name "Net-(U27-RXD)") (class "Default")
      (node (ref "R127") (pin "2") (pinfunction "2_2") (pintype "passive"))
      (node (ref "U27") (pin "2") (pinfunction "RXD_2") (pintype "passive"))
    )
    (net (code "44") (name "Net-(U27-TXD)") (class "Default")
      (node (ref "R128") (pin "2") (pinfunction "2_2") (pintype "passive"))
      (node (ref "U27") (pin "3") (pinfunction "TXD_3") (pintype "passive"))
    )
    (net (code "45") (name "Net-(U29-C1+)") (class "Default")
      (node (ref "C109") (pin "1") (pinfunction "1_1") (pintype "passive"))
      (node (ref "U29") (pin "1") (pinfunction "C1+_1") (pintype "passive"))
    )
    (net (code "46") (name "Net-(U29-C1-)") (class "Default")
      (node (ref "C109") (pin "2") (pinfunction "2_2") (pintype "passive"))
      (node (ref "U29") (pin "3") (pinfunction "C1-_3") (pintype "passive"))
    )
    (net (code "47") (name "Net-(U29-C2+)") (class "Default")
      (node (ref "C110") (pin "1") (pinfunction "1_1") (pintype "passive"))
      (node (ref "U29") (pin "4") (pinfunction "C2+_4") (pintype "passive"))
    )
    (net (code "48") (name "Net-(U29-C2-)") (class "Default")
      (node (ref "C110") (pin "2") (pinfunction "2_2") (pintype "passive"))
      (node (ref "U29") (pin "5") (pinfunction "C2-_5") (pintype "passive"))
    )
    (net (code "49") (name "Net-(U29-V+)") (class "Default")
      (node (ref "C111") (pin "1") (pinfunction "1_1") (pintype "passive"))
      (node (ref "U29") (pin "2") (pinfunction "V+_2") (pintype "passive"))
    )
    (net (code "50") (name "Net-(U29-V-)") (class "Default")
      (node (ref "C112") (pin "1") (pinfunction "1_1") (pintype "passive"))
      (node (ref "U29") (pin "6") (pinfunction "V-_6") (pintype "passive"))
    )
    (net (code "51") (name "P2{slash}GPIO3_C7_d{slash}CAN2_nINT{slash}3V3") (class "Default")
      (node (ref "R131") (pin "1") (pinfunction "1_1") (pintype "passive"))
    )
    (net (code "52") (name "P3{slash}UART4_RTSN_M0{slash}RS485_RD{slash}3V3") (class "Default")
      (node (ref "U21") (pin "4") (pinfunction "~{RE}_4") (pintype "passive"))
      (node (ref "U21") (pin "5") (pinfunction "DE_5") (pintype "passive"))
    )
    (net (code "53") (name "R1{slash}UART4_RX_M0{slash}RS485{slash}3V3") (class "Default")
      (node (ref "R111") (pin "2") (pinfunction "2_2") (pintype "passive"))
      (node (ref "U21") (pin "3") (pinfunction "R_3") (pintype "passive"))
    )
    (net (code "54") (name "R2{slash}SPI2_MISO_M0{slash}CAN{slash}3V3") (class "Default")
      (node (ref "R122") (pin "1") (pinfunction "1_1") (pintype "passive"))
      (node (ref "R130") (pin "1") (pinfunction "1_1") (pintype "passive"))
    )
    (net (code "55") (name "R3{slash}UART4_TX_M0{slash}RS485{slash}3V3") (class "Default")
      (node (ref "U21") (pin "6") (pinfunction "D_6") (pintype "passive"))
    )
    (net (code "56") (name "T3{slash}SPI2_MOSI_M0{slash}CAN{slash}3V3") (class "Default")
      (node (ref "C105") (pin "1") (pinfunction "1_1") (pintype "passive"))
      (node (ref "U23") (pin "14") (pinfunction "SI_14") (pintype "passive"))
      (node (ref "U26") (pin "14") (pinfunction "SI_14") (pintype "passive"))
    )
    (net (code "57") (name "VDD_3V3_ACODEC") (class "Default")
      (node (ref "C107") (pin "2") (pinfunction "2_2") (pintype "passive"))
      (node (ref "C108") (pin "2") (pinfunction "2_2") (pintype "passive"))
      (node (ref "U29") (pin "16") (pinfunction "VCC_16") (pintype "passive"))
    )
    (net (code "58") (name "VDD_3V3_MAIN") (class "Default")
      (node (ref "C100") (pin "1") (pinfunction "1_1") (pintype "passive"))
      (node (ref "C77") (pin "1") (pinfunction "1_1") (pintype "passive"))
      (node (ref "C78") (pin "1") (pinfunction "1_1") (pintype "passive"))
      (node (ref "C85") (pin "1") (pinfunction "1_1") (pintype "passive"))
      (node (ref "C86") (pin "1") (pinfunction "1_1") (pintype "passive"))
      (node (ref "C89") (pin "1") (pinfunction "1_1") (pintype "passive"))
      (node (ref "C90") (pin "1") (pinfunction "1_1") (pintype "passive"))
      (node (ref "C99") (pin "1") (pinfunction "1_1") (pintype "passive"))
      (node (ref "R111") (pin "1") (pinfunction "1_1") (pintype "passive"))
      (node (ref "R117") (pin "2") (pinfunction "2_2") (pintype "passive"))
      (node (ref "R118") (pin "2") (pinfunction "2_2") (pintype "passive"))
      (node (ref "R125") (pin "2") (pinfunction "2_2") (pintype "passive"))
      (node (ref "R126") (pin "2") (pinfunction "2_2") (pintype "passive"))
      (node (ref "R99") (pin "1") (pinfunction "1_1") (pintype "passive"))
      (node (ref "U15") (pin "1") (pinfunction "Vcc1_1") (pintype "passive"))
      (node (ref "U21") (pin "1") (pinfunction "Vcc1_1") (pintype "passive"))
      (node (ref "U23") (pin "18") (pinfunction "VDD_18") (pintype "power_in"))
      (node (ref "U24") (pin "1") (pinfunction "VCC1_1") (pintype "power_in"))
      (node (ref "U26") (pin "18") (pinfunction "VDD_18") (pintype "power_in"))
      (node (ref "U27") (pin "1") (pinfunction "VCC1_1") (pintype "power_in"))
    )
    (net (code "59") (name "VDD_5V_ISO") (class "Default")
      (node (ref "C101") (pin "1") (pinfunction "1_1") (pintype "passive"))
      (node (ref "C91") (pin "1") (pinfunction "1_1") (pintype "passive"))
      (node (ref "C97") (pin "1") (pinfunction "1_1") (pintype "passive"))
      (node (ref "C98") (pin "1") (pinfunction "1_1") (pintype "passive"))
      (node (ref "MK1") (pin "4") (pinfunction "+Vo_4") (pintype "passive"))
      (node (ref "R100") (pin "1") (pinfunction "1_1") (pintype "passive"))
      (node (ref "R112") (pin "1") (pinfunction "1_1") (pintype "passive"))
      (node (ref "U15") (pin "16") (pinfunction "Vcc2_16") (pintype "passive"))
      (node (ref "U21") (pin "16") (pinfunction "Vcc2_16") (pintype "passive"))
      (node (ref "U24") (pin "8") (pinfunction "VCC2_8") (pintype "power_in"))
      (node (ref "U27") (pin "8") (pinfunction "VCC2_8") (pintype "power_in"))
    )
    (net (code "60") (name "VDD_5V_MAIN") (class "Default")
      (node (ref "C95") (pin "1") (pinfunction "1_1") (pintype "passive"))
      (node (ref "C96") (pin "1") (pinfunction "1_1") (pintype "passive"))
      (node (ref "MK1") (pin "2") (pinfunction "+Vin_2") (pintype "passive"))
    )
    (net (code "61") (name "XL9555_P12{slash}CAN_nRST{slash}3V3") (class "Default")
      (node (ref "R124") (pin "1") (pinfunction "1_1") (pintype "passive"))
      (node (ref "R132") (pin "1") (pinfunction "1_1") (pintype "passive"))
    )
    (net (code "62") (name "unconnected-(CON9-CTS-Pad8)") (class "Default")
      (node (ref "CON9") (pin "8") (pinfunction "CTS_8") (pintype "passive+no_connect"))
    )
    (net (code "63") (name "unconnected-(CON9-DCD-Pad1)") (class "Default")
      (node (ref "CON9") (pin "1") (pinfunction "DCD_1") (pintype "passive+no_connect"))
    )
    (net (code "64") (name "unconnected-(CON9-DSR-Pad6)") (class "Default")
      (node (ref "CON9") (pin "6") (pinfunction "DSR_6") (pintype "passive+no_connect"))
    )
    (net (code "65") (name "unconnected-(CON9-DTR-Pad4)") (class "Default")
      (node (ref "CON9") (pin "4") (pinfunction "DTR_4") (pintype "passive+no_connect"))
    )
    (net (code "66") (name "unconnected-(CON9-RI-Pad9)") (class "Default")
      (node (ref "CON9") (pin "9") (pinfunction "RI_9") (pintype "passive+no_connect"))
    )
    (net (code "67") (name "unconnected-(CON9-RTS-Pad7)") (class "Default")
      (node (ref "CON9") (pin "7") (pinfunction "RTS_7") (pintype "passive+no_connect"))
    )
    (net (code "68") (name "unconnected-(J6-Pad1)") (class "Default")
      (node (ref "J6") (pin "1") (pinfunction "1_1") (pintype "passive"))
    )
    (net (code "69") (name "unconnected-(J6-Pad2)") (class "Default")
      (node (ref "J6") (pin "2") (pinfunction "2_2") (pintype "passive"))
    )
    (net (code "70") (name "unconnected-(J6-Pad4)") (class "Default")
      (node (ref "J6") (pin "4") (pinfunction "4_4") (pintype "passive"))
    )
    (net (code "71") (name "unconnected-(J6-Pad5)") (class "Default")
      (node (ref "J6") (pin "5") (pinfunction "5_5") (pintype "passive"))
    )
    (net (code "72") (name "unconnected-(U15-NC-Pad11)") (class "Default")
      (node (ref "U15") (pin "11") (pinfunction "NC_11") (pintype "passive+no_connect"))
    )
    (net (code "73") (name "unconnected-(U15-NC1-Pad14)") (class "Default")
      (node (ref "U15") (pin "14") (pinfunction "NC1_14") (pintype "passive+no_connect"))
    )
    (net (code "74") (name "unconnected-(U21-NC-Pad11)") (class "Default")
      (node (ref "U21") (pin "11") (pinfunction "NC_11") (pintype "passive+no_connect"))
    )
    (net (code "75") (name "unconnected-(U21-NC1-Pad14)") (class "Default")
      (node (ref "U21") (pin "14") (pinfunction "NC1_14") (pintype "passive+no_connect"))
    )
    (net (code "76") (name "unconnected-(U23-CLKOUT-Pad3)") (class "Default")
      (node (ref "U23") (pin "3") (pinfunction "CLKOUT_3") (pintype "passive+no_connect"))
    )
    (net (code "77") (name "unconnected-(U23-nRX0BF-Pad11)") (class "Default")
      (node (ref "U23") (pin "11") (pinfunction "nRX0BF_11") (pintype "passive+no_connect"))
    )
    (net (code "78") (name "unconnected-(U23-nRX1BF-Pad10)") (class "Default")
      (node (ref "U23") (pin "10") (pinfunction "nRX1BF_10") (pintype "passive+no_connect"))
    )
    (net (code "79") (name "unconnected-(U23-nTX0TRS-Pad4)") (class "Default")
      (node (ref "U23") (pin "4") (pinfunction "nTX0TRS_4") (pintype "passive+no_connect"))
    )
    (net (code "80") (name "unconnected-(U23-nTX1TRS-Pad5)") (class "Default")
      (node (ref "U23") (pin "5") (pinfunction "nTX1TRS_5") (pintype "passive+no_connect"))
    )
    (net (code "81") (name "unconnected-(U23-nTX2TRS-Pad6)") (class "Default")
      (node (ref "U23") (pin "6") (pinfunction "nTX2TRS_6") (pintype "passive+no_connect"))
    )
    (net (code "82") (name "unconnected-(U26-CLKOUT-Pad3)") (class "Default")
      (node (ref "U26") (pin "3") (pinfunction "CLKOUT_3") (pintype "passive+no_connect"))
    )
    (net (code "83") (name "unconnected-(U26-nRX0BF-Pad11)") (class "Default")
      (node (ref "U26") (pin "11") (pinfunction "nRX0BF_11") (pintype "passive+no_connect"))
    )
    (net (code "84") (name "unconnected-(U26-nRX1BF-Pad10)") (class "Default")
      (node (ref "U26") (pin "10") (pinfunction "nRX1BF_10") (pintype "passive+no_connect"))
    )
    (net (code "85") (name "unconnected-(U26-nTX0TRS-Pad4)") (class "Default")
      (node (ref "U26") (pin "4") (pinfunction "nTX0TRS_4") (pintype "passive+no_connect"))
    )
    (net (code "86") (name "unconnected-(U26-nTX1TRS-Pad5)") (class "Default")
      (node (ref "U26") (pin "5") (pinfunction "nTX1TRS_5") (pintype "passive+no_connect"))
    )
    (net (code "87") (name "unconnected-(U26-nTX2TRS-Pad6)") (class "Default")
      (node (ref "U26") (pin "6") (pinfunction "nTX2TRS_6") (pintype "passive+no_connect"))
    )
    (net (code "88") (name "unconnected-(U29-R2in-Pad8)") (class "Default")
      (node (ref "U29") (pin "8") (pinfunction "R2in_8") (pintype "passive+no_connect"))
    )
    (net (code "89") (name "unconnected-(U29-R2out-Pad9)") (class "Default")
      (node (ref "U29") (pin "9") (pinfunction "R2out_9") (pintype "passive+no_connect"))
    )
    (net (code "90") (name "unconnected-(U29-T2in-Pad10)") (class "Default")
      (node (ref "U29") (pin "10") (pinfunction "T2in_10") (pintype "passive+no_connect"))
    )
    (net (code "91") (name "unconnected-(U29-T2out-Pad7)") (class "Default")
      (node (ref "U29") (pin "7") (pinfunction "T2out_7") (pintype "passive+no_connect"))
    )
  )
)
